# MicroPomodoro.net
KiCad netlist of a schematic drawn in EAGLE
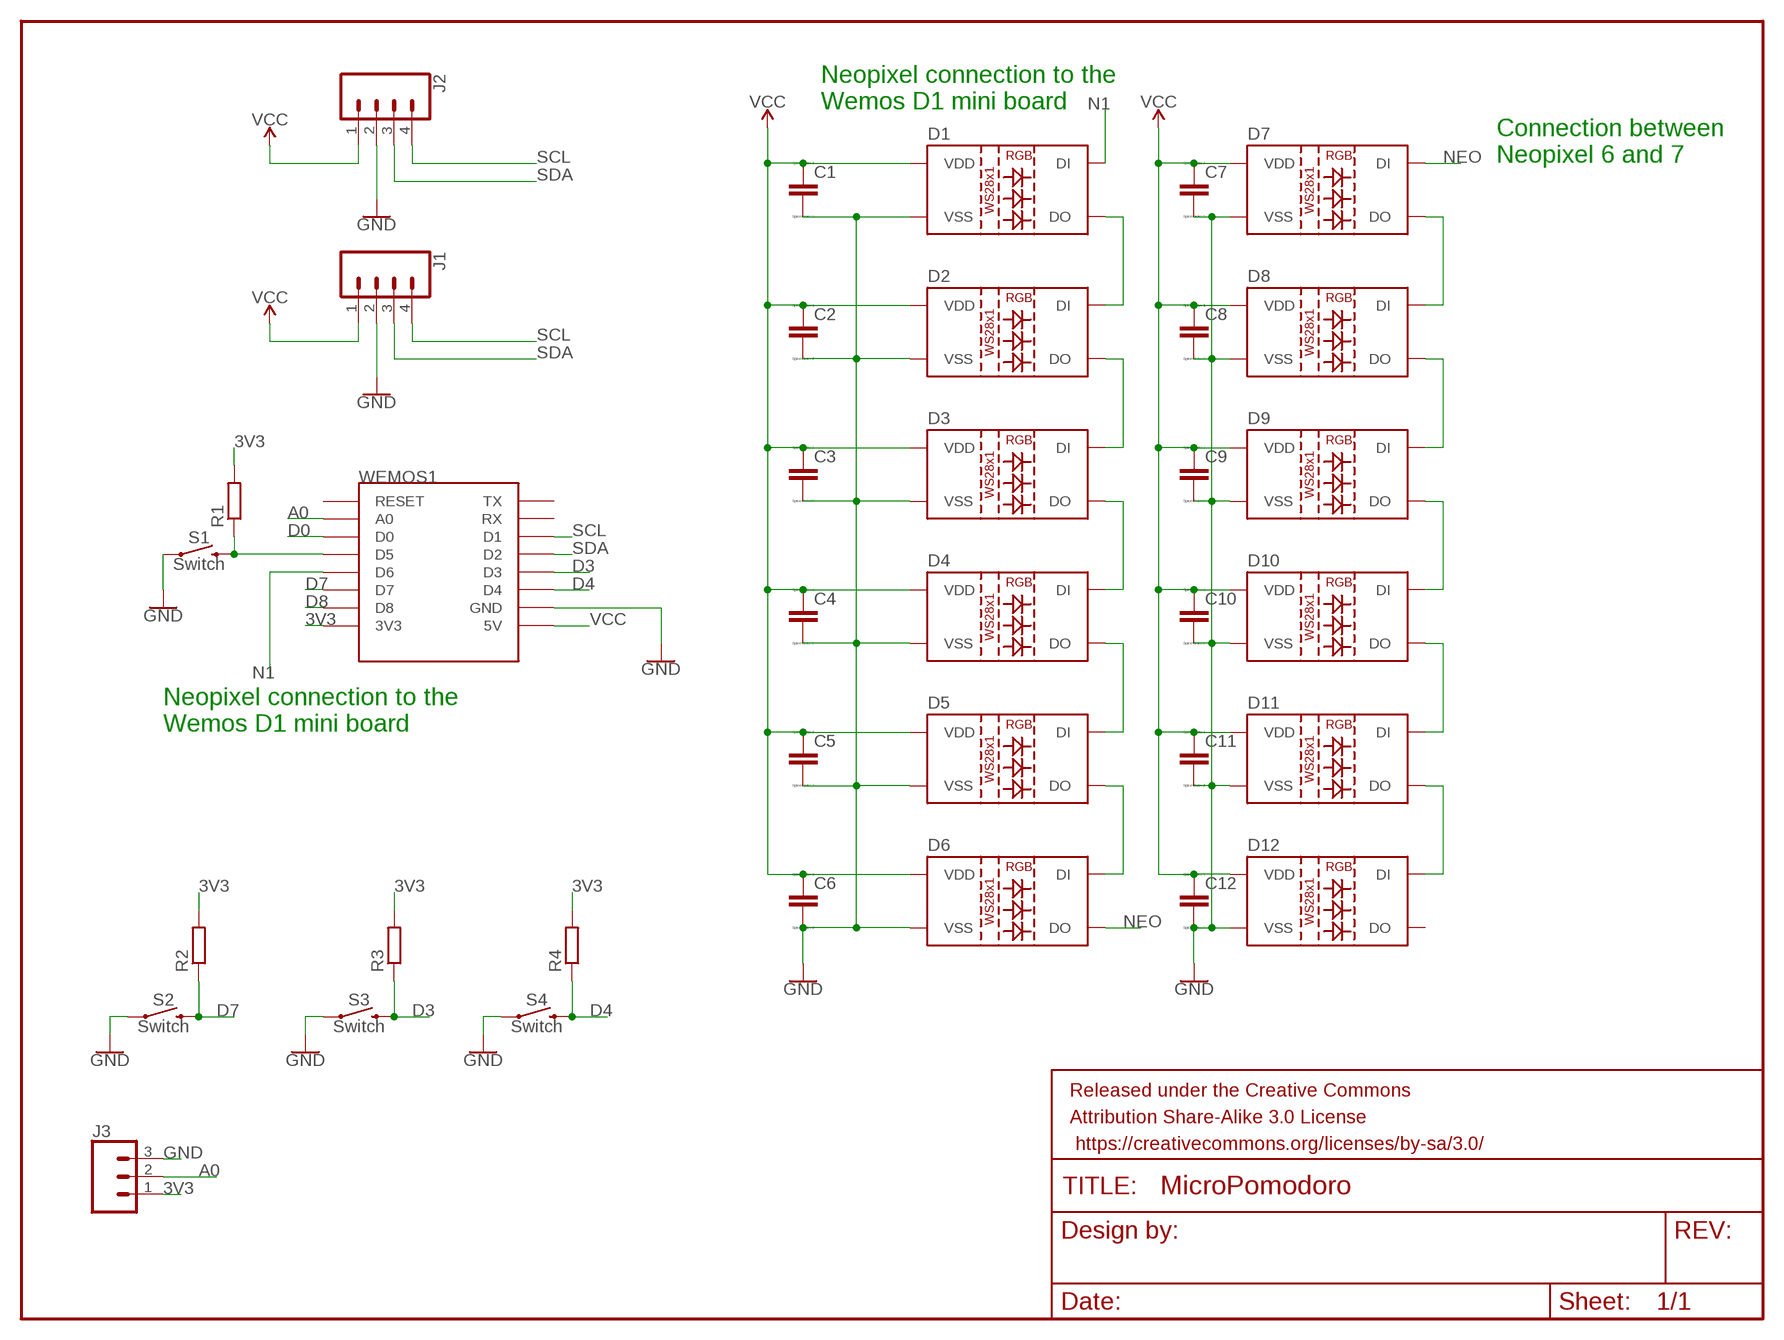
[diagram p0: schematic, sheet 1]

(export (version "E")
  (design (tool "Eeschema 10.0.6"))
  (components
    (comp (ref "C1")
      (value "CC1206")
      (footprint "eagle-import:C1206")
      (libsource (lib "eagle-import") (part "CC1206"))
    )
    (comp (ref "C2")
      (value "CC1206")
      (footprint "eagle-import:C1206")
      (libsource (lib "eagle-import") (part "CC1206"))
    )
    (comp (ref "C3")
      (value "CC1206")
      (footprint "eagle-import:C1206")
      (libsource (lib "eagle-import") (part "CC1206"))
    )
    (comp (ref "C4")
      (value "CC1206")
      (footprint "eagle-import:C1206")
      (libsource (lib "eagle-import") (part "CC1206"))
    )
    (comp (ref "C5")
      (value "CC1206")
      (footprint "eagle-import:C1206")
      (libsource (lib "eagle-import") (part "CC1206"))
    )
    (comp (ref "C6")
      (value "CC1206")
      (footprint "eagle-import:C1206")
      (libsource (lib "eagle-import") (part "CC1206"))
    )
    (comp (ref "C7")
      (value "CC1206")
      (footprint "eagle-import:C1206")
      (libsource (lib "eagle-import") (part "CC1206"))
    )
    (comp (ref "C8")
      (value "CC1206")
      (footprint "eagle-import:C1206")
      (libsource (lib "eagle-import") (part "CC1206"))
    )
    (comp (ref "C9")
      (value "CC1206")
      (footprint "eagle-import:C1206")
      (libsource (lib "eagle-import") (part "CC1206"))
    )
    (comp (ref "C10")
      (value "CC1206")
      (footprint "eagle-import:C1206")
      (libsource (lib "eagle-import") (part "CC1206"))
    )
    (comp (ref "C11")
      (value "CC1206")
      (footprint "eagle-import:C1206")
      (libsource (lib "eagle-import") (part "CC1206"))
    )
    (comp (ref "C12")
      (value "CC1206")
      (footprint "eagle-import:C1206")
      (libsource (lib "eagle-import") (part "CC1206"))
    )
    (comp (ref "D1")
      (value "WS2812B")
      (footprint "eagle-import:WS2812B")
      (libsource (lib "eagle-import") (part "WS2812B"))
    )
    (comp (ref "D2")
      (value "WS2812B")
      (footprint "eagle-import:WS2812B")
      (libsource (lib "eagle-import") (part "WS2812B"))
    )
    (comp (ref "D3")
      (value "WS2812B")
      (footprint "eagle-import:WS2812B")
      (libsource (lib "eagle-import") (part "WS2812B"))
    )
    (comp (ref "D4")
      (value "WS2812B")
      (footprint "eagle-import:WS2812B")
      (libsource (lib "eagle-import") (part "WS2812B"))
    )
    (comp (ref "D5")
      (value "WS2812B")
      (footprint "eagle-import:WS2812B")
      (libsource (lib "eagle-import") (part "WS2812B"))
    )
    (comp (ref "D6")
      (value "WS2812B")
      (footprint "eagle-import:WS2812B")
      (libsource (lib "eagle-import") (part "WS2812B"))
    )
    (comp (ref "D7")
      (value "WS2812B")
      (footprint "eagle-import:WS2812B")
      (libsource (lib "eagle-import") (part "WS2812B"))
    )
    (comp (ref "D8")
      (value "WS2812B")
      (footprint "eagle-import:WS2812B")
      (libsource (lib "eagle-import") (part "WS2812B"))
    )
    (comp (ref "D9")
      (value "WS2812B")
      (footprint "eagle-import:WS2812B")
      (libsource (lib "eagle-import") (part "WS2812B"))
    )
    (comp (ref "D10")
      (value "WS2812B")
      (footprint "eagle-import:WS2812B")
      (libsource (lib "eagle-import") (part "WS2812B"))
    )
    (comp (ref "D11")
      (value "WS2812B")
      (footprint "eagle-import:WS2812B")
      (libsource (lib "eagle-import") (part "WS2812B"))
    )
    (comp (ref "D12")
      (value "WS2812B")
      (footprint "eagle-import:WS2812B")
      (libsource (lib "eagle-import") (part "WS2812B"))
    )
    (comp (ref "FRAME1")
      (value "FRAME-LETTER")
      (footprint "eagle-import:CREATIVE_COMMONS")
      (libsource (lib "eagle-import") (part "FRAME-LETTER"))
    )
    (comp (ref "J1")
      (value "CONN_04LONGPADS")
      (footprint "eagle-import:1X04_LONGPADS")
      (libsource (lib "eagle-import") (part "CONN_04LONGPADS"))
    )
    (comp (ref "J2")
      (value "CONN_04SMD_LONG")
      (footprint "eagle-import:1X04_SMD_LONG_NO_HOLE")
      (libsource (lib "eagle-import") (part "CONN_04SMD_LONG"))
    )
    (comp (ref "J3")
      (value "CONN_03SMD_RA_MALE")
      (footprint "eagle-import:1X03_SMD_RA_MALE")
      (libsource (lib "eagle-import") (part "CONN_03SMD_RA_MALE"))
    )
    (comp (ref "R1")
      (value "R-EU_R1206")
      (footprint "eagle-import:R1206")
      (libsource (lib "eagle-import") (part "R-EU_R1206"))
    )
    (comp (ref "R2")
      (value "R-EU_R1206")
      (footprint "eagle-import:R1206")
      (libsource (lib "eagle-import") (part "R-EU_R1206"))
    )
    (comp (ref "R3")
      (value "R-EU_R1206")
      (footprint "eagle-import:R1206")
      (libsource (lib "eagle-import") (part "R-EU_R1206"))
    )
    (comp (ref "R4")
      (value "R-EU_R1206")
      (footprint "eagle-import:R1206")
      (libsource (lib "eagle-import") (part "R-EU_R1206"))
    )
    (comp (ref "S1")
      (value "Switch")
      (footprint "eagle-import:TACTILE_SWITCH_PTH_6.0MM")
      (libsource (lib "eagle-import") (part "MOMENTARY-SWITCH-SPST-PTH-6.0MM"))
    )
    (comp (ref "S2")
      (value "Switch")
      (footprint "eagle-import:TACTILE_SWITCH_PTH_6.0MM")
      (libsource (lib "eagle-import") (part "MOMENTARY-SWITCH-SPST-PTH-6.0MM"))
    )
    (comp (ref "S3")
      (value "Switch")
      (footprint "eagle-import:TACTILE_SWITCH_PTH_6.0MM")
      (libsource (lib "eagle-import") (part "MOMENTARY-SWITCH-SPST-PTH-6.0MM"))
    )
    (comp (ref "S4")
      (value "Switch")
      (footprint "eagle-import:TACTILE_SWITCH_PTH_6.0MM")
      (libsource (lib "eagle-import") (part "MOMENTARY-SWITCH-SPST-PTH-6.0MM"))
    )
    (comp (ref "WEMOS1")
      (value "WEMOS-D1-MINI")
      (footprint "eagle-import:WEMOS-D1-MINI")
      (libsource (lib "eagle-import") (part "WEMOS-D1-MINI"))
    )
  )
  (nets
    (net (code "1") (name "/3V3") (class "Default")
      (node (ref "J3") (pin "1") (pinfunction "1_1") (pintype "passive"))
      (node (ref "R1") (pin "2") (pinfunction "2_2") (pintype "passive"))
      (node (ref "R2") (pin "2") (pinfunction "2_2") (pintype "passive"))
      (node (ref "R3") (pin "2") (pinfunction "2_2") (pintype "passive"))
      (node (ref "R4") (pin "2") (pinfunction "2_2") (pintype "passive"))
      (node (ref "WEMOS1") (pin "3V3") (pinfunction "3V3_3V3") (pintype "bidirectional"))
    )
    (net (code "2") (name "/A0") (class "Default")
      (node (ref "J3") (pin "2") (pinfunction "2_2") (pintype "passive"))
      (node (ref "WEMOS1") (pin "A0") (pinfunction "A0_A0") (pintype "bidirectional"))
    )
    (net (code "3") (name "/D0") (class "Default")
      (node (ref "WEMOS1") (pin "D0") (pinfunction "D0_D0") (pintype "bidirectional"))
    )
    (net (code "4") (name "/D3") (class "Default")
      (node (ref "R3") (pin "1") (pinfunction "1_1") (pintype "passive"))
      (node (ref "S3") (pin "3") (pinfunction "2_3") (pintype "passive"))
      (node (ref "WEMOS1") (pin "D3") (pinfunction "D3_D3") (pintype "bidirectional"))
    )
    (net (code "5") (name "/D4") (class "Default")
      (node (ref "R4") (pin "1") (pinfunction "1_1") (pintype "passive"))
      (node (ref "S4") (pin "3") (pinfunction "2_3") (pintype "passive"))
      (node (ref "WEMOS1") (pin "D4") (pinfunction "D4_D4") (pintype "bidirectional"))
    )
    (net (code "6") (name "/D7") (class "Default")
      (node (ref "R2") (pin "1") (pinfunction "1_1") (pintype "passive"))
      (node (ref "S2") (pin "3") (pinfunction "2_3") (pintype "passive"))
      (node (ref "WEMOS1") (pin "D7") (pinfunction "D7_D7") (pintype "bidirectional"))
    )
    (net (code "7") (name "/D8") (class "Default")
      (node (ref "WEMOS1") (pin "D8") (pinfunction "D8_D8") (pintype "bidirectional"))
    )
    (net (code "8") (name "/N1") (class "Default")
      (node (ref "D1") (pin "4") (pinfunction "DI_4") (pintype "bidirectional"))
      (node (ref "WEMOS1") (pin "D6") (pinfunction "D6_D6") (pintype "bidirectional"))
    )
    (net (code "9") (name "/NEO") (class "Default")
      (node (ref "D6") (pin "2") (pinfunction "DO_2") (pintype "bidirectional"))
      (node (ref "D7") (pin "4") (pinfunction "DI_4") (pintype "bidirectional"))
    )
    (net (code "10") (name "/SCL") (class "Default")
      (node (ref "J1") (pin "4") (pinfunction "4_4") (pintype "passive"))
      (node (ref "J2") (pin "4") (pinfunction "4_4") (pintype "passive"))
      (node (ref "WEMOS1") (pin "D1") (pinfunction "D1_D1") (pintype "bidirectional"))
    )
    (net (code "11") (name "/SDA") (class "Default")
      (node (ref "J1") (pin "3") (pinfunction "3_3") (pintype "passive"))
      (node (ref "J2") (pin "3") (pinfunction "3_3") (pintype "passive"))
      (node (ref "WEMOS1") (pin "D2") (pinfunction "D2_D2") (pintype "bidirectional"))
    )
    (net (code "12") (name "GND") (class "Default")
      (node (ref "C1") (pin "2") (pinfunction "2_2") (pintype "passive"))
      (node (ref "C10") (pin "2") (pinfunction "2_2") (pintype "passive"))
      (node (ref "C11") (pin "2") (pinfunction "2_2") (pintype "passive"))
      (node (ref "C12") (pin "2") (pinfunction "2_2") (pintype "passive"))
      (node (ref "C2") (pin "2") (pinfunction "2_2") (pintype "passive"))
      (node (ref "C3") (pin "2") (pinfunction "2_2") (pintype "passive"))
      (node (ref "C4") (pin "2") (pinfunction "2_2") (pintype "passive"))
      (node (ref "C5") (pin "2") (pinfunction "2_2") (pintype "passive"))
      (node (ref "C6") (pin "2") (pinfunction "2_2") (pintype "passive"))
      (node (ref "C7") (pin "2") (pinfunction "2_2") (pintype "passive"))
      (node (ref "C8") (pin "2") (pinfunction "2_2") (pintype "passive"))
      (node (ref "C9") (pin "2") (pinfunction "2_2") (pintype "passive"))
      (node (ref "D1") (pin "3") (pinfunction "VSS_3") (pintype "bidirectional"))
      (node (ref "D10") (pin "3") (pinfunction "VSS_3") (pintype "bidirectional"))
      (node (ref "D11") (pin "3") (pinfunction "VSS_3") (pintype "bidirectional"))
      (node (ref "D12") (pin "3") (pinfunction "VSS_3") (pintype "bidirectional"))
      (node (ref "D2") (pin "3") (pinfunction "VSS_3") (pintype "bidirectional"))
      (node (ref "D3") (pin "3") (pinfunction "VSS_3") (pintype "bidirectional"))
      (node (ref "D4") (pin "3") (pinfunction "VSS_3") (pintype "bidirectional"))
      (node (ref "D5") (pin "3") (pinfunction "VSS_3") (pintype "bidirectional"))
      (node (ref "D6") (pin "3") (pinfunction "VSS_3") (pintype "bidirectional"))
      (node (ref "D7") (pin "3") (pinfunction "VSS_3") (pintype "bidirectional"))
      (node (ref "D8") (pin "3") (pinfunction "VSS_3") (pintype "bidirectional"))
      (node (ref "D9") (pin "3") (pinfunction "VSS_3") (pintype "bidirectional"))
      (node (ref "J1") (pin "2") (pinfunction "2_2") (pintype "passive"))
      (node (ref "J2") (pin "2") (pinfunction "2_2") (pintype "passive"))
      (node (ref "J3") (pin "3") (pinfunction "3_3") (pintype "passive"))
      (node (ref "S1") (pin "1") (pinfunction "1_1") (pintype "passive"))
      (node (ref "S2") (pin "1") (pinfunction "1_1") (pintype "passive"))
      (node (ref "S3") (pin "1") (pinfunction "1_1") (pintype "passive"))
      (node (ref "S4") (pin "1") (pinfunction "1_1") (pintype "passive"))
      (node (ref "WEMOS1") (pin "GND") (pinfunction "GND_GND") (pintype "bidirectional"))
    )
    (net (code "13") (name "Net-(D1-DO)") (class "Default")
      (node (ref "D1") (pin "2") (pinfunction "DO_2") (pintype "bidirectional"))
      (node (ref "D2") (pin "4") (pinfunction "DI_4") (pintype "bidirectional"))
    )
    (net (code "14") (name "Net-(D2-DO)") (class "Default")
      (node (ref "D2") (pin "2") (pinfunction "DO_2") (pintype "bidirectional"))
      (node (ref "D3") (pin "4") (pinfunction "DI_4") (pintype "bidirectional"))
    )
    (net (code "15") (name "Net-(D3-DO)") (class "Default")
      (node (ref "D3") (pin "2") (pinfunction "DO_2") (pintype "bidirectional"))
      (node (ref "D4") (pin "4") (pinfunction "DI_4") (pintype "bidirectional"))
    )
    (net (code "16") (name "Net-(D4-DO)") (class "Default")
      (node (ref "D4") (pin "2") (pinfunction "DO_2") (pintype "bidirectional"))
      (node (ref "D5") (pin "4") (pinfunction "DI_4") (pintype "bidirectional"))
    )
    (net (code "17") (name "Net-(D5-DO)") (class "Default")
      (node (ref "D5") (pin "2") (pinfunction "DO_2") (pintype "bidirectional"))
      (node (ref "D6") (pin "4") (pinfunction "DI_4") (pintype "bidirectional"))
    )
    (net (code "18") (name "Net-(D7-DO)") (class "Default")
      (node (ref "D7") (pin "2") (pinfunction "DO_2") (pintype "bidirectional"))
      (node (ref "D8") (pin "4") (pinfunction "DI_4") (pintype "bidirectional"))
    )
    (net (code "19") (name "Net-(D8-DO)") (class "Default")
      (node (ref "D8") (pin "2") (pinfunction "DO_2") (pintype "bidirectional"))
      (node (ref "D9") (pin "4") (pinfunction "DI_4") (pintype "bidirectional"))
    )
    (net (code "20") (name "Net-(D10-DI)") (class "Default")
      (node (ref "D10") (pin "4") (pinfunction "DI_4") (pintype "bidirectional"))
      (node (ref "D9") (pin "2") (pinfunction "DO_2") (pintype "bidirectional"))
    )
    (net (code "21") (name "Net-(D10-DO)") (class "Default")
      (node (ref "D10") (pin "2") (pinfunction "DO_2") (pintype "bidirectional"))
      (node (ref "D11") (pin "4") (pinfunction "DI_4") (pintype "bidirectional"))
    )
    (net (code "22") (name "Net-(D11-DO)") (class "Default")
      (node (ref "D11") (pin "2") (pinfunction "DO_2") (pintype "bidirectional"))
      (node (ref "D12") (pin "4") (pinfunction "DI_4") (pintype "bidirectional"))
    )
    (net (code "23") (name "Net-(S1-2)") (class "Default")
      (node (ref "R1") (pin "1") (pinfunction "1_1") (pintype "passive"))
      (node (ref "S1") (pin "3") (pinfunction "2_3") (pintype "passive"))
      (node (ref "WEMOS1") (pin "D5") (pinfunction "D5_D5") (pintype "bidirectional"))
    )
    (net (code "24") (name "VCC") (class "Default")
      (node (ref "C1") (pin "1") (pinfunction "1_1") (pintype "passive"))
      (node (ref "C10") (pin "1") (pinfunction "1_1") (pintype "passive"))
      (node (ref "C11") (pin "1") (pinfunction "1_1") (pintype "passive"))
      (node (ref "C12") (pin "1") (pinfunction "1_1") (pintype "passive"))
      (node (ref "C2") (pin "1") (pinfunction "1_1") (pintype "passive"))
      (node (ref "C3") (pin "1") (pinfunction "1_1") (pintype "passive"))
      (node (ref "C4") (pin "1") (pinfunction "1_1") (pintype "passive"))
      (node (ref "C5") (pin "1") (pinfunction "1_1") (pintype "passive"))
      (node (ref "C6") (pin "1") (pinfunction "1_1") (pintype "passive"))
      (node (ref "C7") (pin "1") (pinfunction "1_1") (pintype "passive"))
      (node (ref "C8") (pin "1") (pinfunction "1_1") (pintype "passive"))
      (node (ref "C9") (pin "1") (pinfunction "1_1") (pintype "passive"))
      (node (ref "D1") (pin "1") (pinfunction "VDD_1") (pintype "bidirectional"))
      (node (ref "D10") (pin "1") (pinfunction "VDD_1") (pintype "bidirectional"))
      (node (ref "D11") (pin "1") (pinfunction "VDD_1") (pintype "bidirectional"))
      (node (ref "D12") (pin "1") (pinfunction "VDD_1") (pintype "bidirectional"))
      (node (ref "D2") (pin "1") (pinfunction "VDD_1") (pintype "bidirectional"))
      (node (ref "D3") (pin "1") (pinfunction "VDD_1") (pintype "bidirectional"))
      (node (ref "D4") (pin "1") (pinfunction "VDD_1") (pintype "bidirectional"))
      (node (ref "D5") (pin "1") (pinfunction "VDD_1") (pintype "bidirectional"))
      (node (ref "D6") (pin "1") (pinfunction "VDD_1") (pintype "bidirectional"))
      (node (ref "D7") (pin "1") (pinfunction "VDD_1") (pintype "bidirectional"))
      (node (ref "D8") (pin "1") (pinfunction "VDD_1") (pintype "bidirectional"))
      (node (ref "D9") (pin "1") (pinfunction "VDD_1") (pintype "bidirectional"))
      (node (ref "J1") (pin "1") (pinfunction "1_1") (pintype "passive"))
      (node (ref "J2") (pin "1") (pinfunction "1_1") (pintype "passive"))
      (node (ref "WEMOS1") (pin "5V") (pinfunction "5V_5V") (pintype "bidirectional"))
    )
    (net (code "25") (name "unconnected-(D12-DO-Pad2)") (class "Default")
      (node (ref "D12") (pin "2") (pinfunction "DO_2") (pintype "bidirectional"))
    )
    (net (code "26") (name "unconnected-(WEMOS1-PadRESET)") (class "Default")
      (node (ref "WEMOS1") (pin "RESET") (pinfunction "RESET_RESET") (pintype "bidirectional"))
    )
    (net (code "27") (name "unconnected-(WEMOS1-PadRX)") (class "Default")
      (node (ref "WEMOS1") (pin "RX") (pinfunction "RX_RX") (pintype "bidirectional"))
    )
    (net (code "28") (name "unconnected-(WEMOS1-PadTX)") (class "Default")
      (node (ref "WEMOS1") (pin "TX") (pinfunction "TX_TX") (pintype "bidirectional"))
    )
  )
)
